# mainboardShield.net
KiCad netlist of a schematic drawn in EAGLE
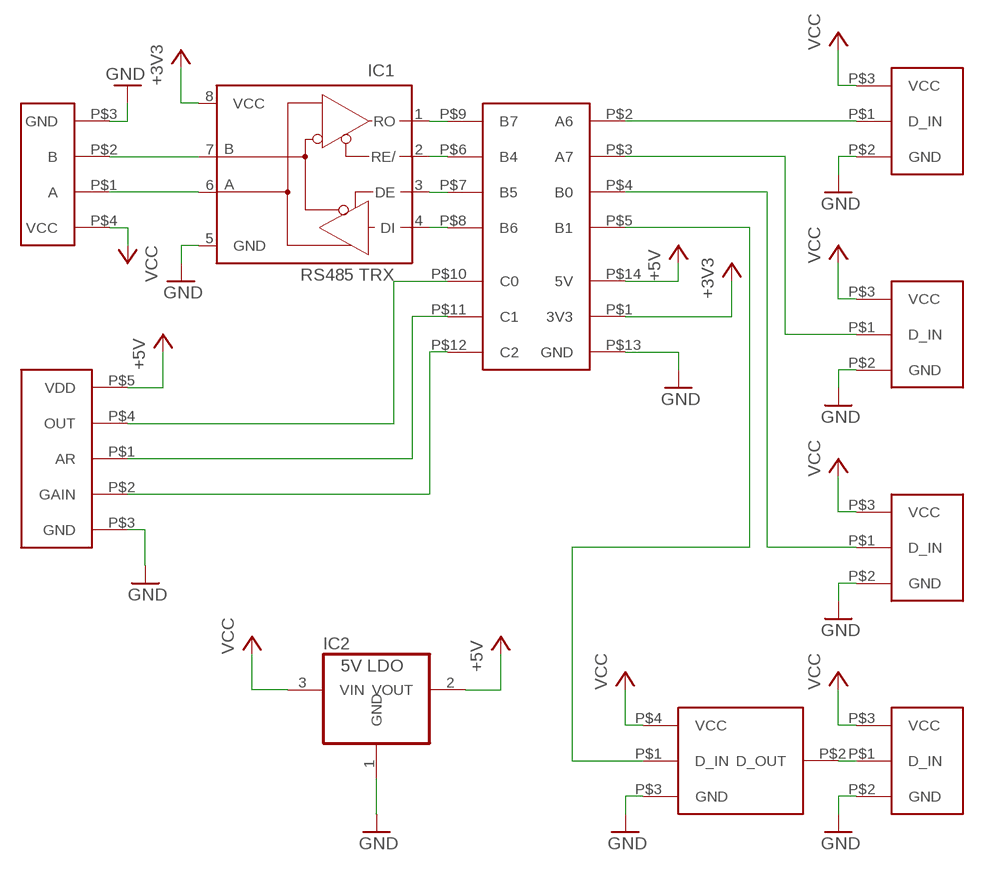
[diagram p0: schematic, sheet 1]

(export (version "E")
  (design (tool "Eeschema 10.0.6"))
  (components
    (comp (ref "IC1")
      (value "RS485 TRX")
      (footprint "eagle-import:DIL08")
      (libsource (lib "eagle-import") (part "MAX34PA69E"))
    )
    (comp (ref "IC2")
      (value "5V LDO")
      (footprint "eagle-import:DD-3")
      (fields (field (name "MF") "TEXAS INSTRUMENTS") (field (name "MPN") "REG1117FAKTTT"))
      (libsource (lib "eagle-import") (part "REG1117F"))
    )
    (comp (ref "LEDSTRIP")
      (value "LEDSTRIP")
      (footprint "eagle-import:LEDSTRIPDUMMY")
      (libsource (lib "eagle-import") (part "LEDSTRIP"))
    )
    (comp (ref "STM32")
      (value "STM32F411E-DISCO")
      (footprint "eagle-import:STM32F411E-DISCO")
      (libsource (lib "eagle-import") (part "STM32F411E-DISCO"))
    )
    (comp (ref "U$1")
      (value "LEDDISPLAY")
      (footprint "eagle-import:LEDDISPLAYDUMMY")
      (libsource (lib "eagle-import") (part "LEDDISPLAY"))
    )
    (comp (ref "U$2")
      (value "LEDSTRIP")
      (footprint "eagle-import:LEDSTRIPDUMMY")
      (libsource (lib "eagle-import") (part "LEDSTRIP"))
    )
    (comp (ref "U$3")
      (value "LEDSTRIP")
      (footprint "eagle-import:LEDSTRIPDUMMY")
      (libsource (lib "eagle-import") (part "LEDSTRIP"))
    )
    (comp (ref "U$4")
      (value "LEDSTRIP")
      (footprint "eagle-import:LEDSTRIPDUMMY")
      (libsource (lib "eagle-import") (part "LEDSTRIP"))
    )
    (comp (ref "U$5")
      (value "ADAFRUITMIC")
      (footprint "eagle-import:ADAFRUITMIC")
      (libsource (lib "eagle-import") (part "ADAFRUITMIC"))
    )
    (comp (ref "U$6")
      (value "BUS")
      (footprint "eagle-import:BUS")
      (libsource (lib "eagle-import") (part "BUS"))
    )
  )
  (nets
    (net (code "1") (name "+3V3") (class "Default")
      (node (ref "IC1") (pin "8") (pinfunction "VCC_8") (pintype "power_in"))
      (node (ref "STM32") (pin "P$1") (pinfunction "3V3_P$1") (pintype "bidirectional"))
    )
    (net (code "2") (name "+5V") (class "Default")
      (node (ref "IC2") (pin "2") (pinfunction "VOUT_2") (pintype "output"))
      (node (ref "STM32") (pin "P$14") (pinfunction "5V_P$14") (pintype "bidirectional"))
      (node (ref "U$5") (pin "P$5") (pinfunction "VDD_P$5") (pintype "bidirectional"))
    )
    (net (code "3") (name "GND") (class "Default")
      (node (ref "IC1") (pin "5") (pinfunction "GND_5") (pintype "power_in"))
      (node (ref "IC2") (pin "1") (pinfunction "GND_1") (pintype "power_in"))
      (node (ref "LEDSTRIP") (pin "P$2") (pinfunction "GND_P$2") (pintype "bidirectional"))
      (node (ref "STM32") (pin "P$13") (pinfunction "GND_P$13") (pintype "bidirectional"))
      (node (ref "U$1") (pin "P$3") (pinfunction "GND_P$3") (pintype "bidirectional"))
      (node (ref "U$2") (pin "P$2") (pinfunction "GND_P$2") (pintype "bidirectional"))
      (node (ref "U$3") (pin "P$2") (pinfunction "GND_P$2") (pintype "bidirectional"))
      (node (ref "U$4") (pin "P$2") (pinfunction "GND_P$2") (pintype "bidirectional"))
      (node (ref "U$5") (pin "P$3") (pinfunction "GND_P$3") (pintype "bidirectional"))
      (node (ref "U$6") (pin "P$3") (pinfunction "GND_P$3") (pintype "bidirectional"))
    )
    (net (code "4") (name "Net-(IC1-A)") (class "Default")
      (node (ref "IC1") (pin "6") (pinfunction "A_6") (pintype "passive"))
      (node (ref "U$6") (pin "P$1") (pinfunction "A_P$1") (pintype "bidirectional"))
    )
    (net (code "5") (name "Net-(IC1-B)") (class "Default")
      (node (ref "IC1") (pin "7") (pinfunction "B_7") (pintype "passive"))
      (node (ref "U$6") (pin "P$2") (pinfunction "B_P$2") (pintype "bidirectional"))
    )
    (net (code "6") (name "Net-(IC1-DE)") (class "Default")
      (node (ref "IC1") (pin "3") (pinfunction "DE_3") (pintype "input"))
      (node (ref "STM32") (pin "P$7") (pinfunction "B5_P$7") (pintype "bidirectional"))
    )
    (net (code "7") (name "Net-(IC1-DI)") (class "Default")
      (node (ref "IC1") (pin "4") (pinfunction "DI_4") (pintype "input"))
      (node (ref "STM32") (pin "P$8") (pinfunction "B6_P$8") (pintype "bidirectional"))
    )
    (net (code "8") (name "Net-(IC1-RE{slash})") (class "Default")
      (node (ref "IC1") (pin "2") (pinfunction "RE/_2") (pintype "input"))
      (node (ref "STM32") (pin "P$6") (pinfunction "B4_P$6") (pintype "bidirectional"))
    )
    (net (code "9") (name "Net-(IC1-RO)") (class "Default")
      (node (ref "IC1") (pin "1") (pinfunction "RO_1") (pintype "output"))
      (node (ref "STM32") (pin "P$9") (pinfunction "B7_P$9") (pintype "bidirectional"))
    )
    (net (code "10") (name "Net-(LEDSTRIP-D_IN)") (class "Default")
      (node (ref "LEDSTRIP") (pin "P$1") (pinfunction "D_IN_P$1") (pintype "bidirectional"))
      (node (ref "STM32") (pin "P$2") (pinfunction "A6_P$2") (pintype "bidirectional"))
    )
    (net (code "11") (name "Net-(STM32-A7)") (class "Default")
      (node (ref "STM32") (pin "P$3") (pinfunction "A7_P$3") (pintype "bidirectional"))
      (node (ref "U$2") (pin "P$1") (pinfunction "D_IN_P$1") (pintype "bidirectional"))
    )
    (net (code "12") (name "Net-(STM32-B0)") (class "Default")
      (node (ref "STM32") (pin "P$4") (pinfunction "B0_P$4") (pintype "bidirectional"))
      (node (ref "U$4") (pin "P$1") (pinfunction "D_IN_P$1") (pintype "bidirectional"))
    )
    (net (code "13") (name "Net-(STM32-B1)") (class "Default")
      (node (ref "STM32") (pin "P$5") (pinfunction "B1_P$5") (pintype "bidirectional"))
      (node (ref "U$1") (pin "P$1") (pinfunction "D_IN_P$1") (pintype "bidirectional"))
    )
    (net (code "14") (name "Net-(STM32-C0)") (class "Default")
      (node (ref "STM32") (pin "P$10") (pinfunction "C0_P$10") (pintype "bidirectional"))
      (node (ref "U$5") (pin "P$4") (pinfunction "OUT_P$4") (pintype "bidirectional"))
    )
    (net (code "15") (name "Net-(STM32-C1)") (class "Default")
      (node (ref "STM32") (pin "P$11") (pinfunction "C1_P$11") (pintype "bidirectional"))
      (node (ref "U$5") (pin "P$1") (pinfunction "AR_P$1") (pintype "bidirectional"))
    )
    (net (code "16") (name "Net-(STM32-C2)") (class "Default")
      (node (ref "STM32") (pin "P$12") (pinfunction "C2_P$12") (pintype "bidirectional"))
      (node (ref "U$5") (pin "P$2") (pinfunction "GAIN_P$2") (pintype "bidirectional"))
    )
    (net (code "17") (name "Net-(U$1-D_OUT)") (class "Default")
      (node (ref "U$1") (pin "P$2") (pinfunction "D_OUT_P$2") (pintype "bidirectional"))
      (node (ref "U$3") (pin "P$1") (pinfunction "D_IN_P$1") (pintype "bidirectional"))
    )
    (net (code "18") (name "VCC") (class "Default")
      (node (ref "IC2") (pin "3") (pinfunction "VIN_3") (pintype "input"))
      (node (ref "LEDSTRIP") (pin "P$3") (pinfunction "VCC_P$3") (pintype "bidirectional"))
      (node (ref "U$1") (pin "P$4") (pinfunction "VCC_P$4") (pintype "bidirectional"))
      (node (ref "U$2") (pin "P$3") (pinfunction "VCC_P$3") (pintype "bidirectional"))
      (node (ref "U$3") (pin "P$3") (pinfunction "VCC_P$3") (pintype "bidirectional"))
      (node (ref "U$4") (pin "P$3") (pinfunction "VCC_P$3") (pintype "bidirectional"))
      (node (ref "U$6") (pin "P$4") (pinfunction "VCC_P$4") (pintype "bidirectional"))
    )
  )
)
